# DC-DC.net
KiCad netlist of a schematic drawn in Altium Designer
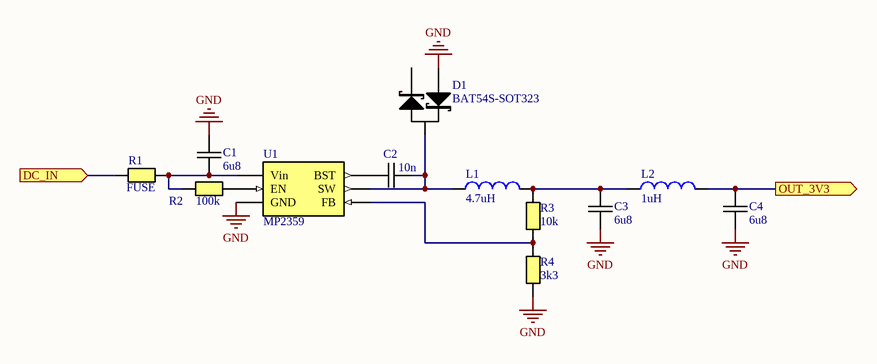
[diagram p0: DC-DC.SchDoc]

(export (version "E")
  (design (tool "Eeschema 10.0.6"))
  (components
    (comp (ref "C1")
      (value "6u8")
      (footprint "CAPC0805(2012)75_N")
      (description "Ceramic capacitor Medium density")
      (libsource (lib "Discrete_Passive_RCL") (part "Capacitor M"))
    )
    (comp (ref "C2")
      (value "10n")
      (footprint "CAPC0603(1608)55_N")
      (description "Ceramic capacitor Medium density")
      (libsource (lib "Discrete_Passive_RCL") (part "Capacitor M"))
    )
    (comp (ref "C3")
      (value "6u8")
      (footprint "CAPC0805(2012)75_N")
      (description "Ceramic capacitor Medium density")
      (libsource (lib "Discrete_Passive_RCL") (part "Capacitor M"))
    )
    (comp (ref "C4")
      (value "6u8")
      (footprint "CAPC0805(2012)75_N")
      (description "Ceramic capacitor Medium density")
      (libsource (lib "Discrete_Passive_RCL") (part "Capacitor M"))
    )
    (comp (ref "D1")
      (value "BAT54S-SOT323")
      (footprint "SOT323-123")
      (description "DUAL SCHOTTKY DIODE SERIES")
      (fields
        (field (name "MANUFACTURER") "NXP Semiconductors")
        (field (name "MANUFACTURER PART NUMBER") "BAT54SW,115")
      )
      (libsource (lib "vh_altium_library") (part "BAT54S-SOT323"))
    )
    (comp (ref "L1")
      (value "IND")
      (footprint "C_1210")
      (fields (field (name "INDUCTANCE") "4.7uH"))
      (libsource (lib "MyLibAltium_v1") (part "Inductor"))
    )
    (comp (ref "L2")
      (value "IND")
      (footprint "C_1206")
      (fields (field (name "INDUCTANCE") "1uH"))
      (libsource (lib "MyLibAltium_v1") (part "Inductor"))
    )
    (comp (ref "R1")
      (value "100")
      (footprint "RESC0805(2012)_N")
      (description "Resistor Medium Density")
      (libsource (lib "Discrete_Passive_RCL") (part "Resistor M"))
    )
    (comp (ref "R2")
      (value "100k")
      (footprint "RESC0805(2012)_N")
      (description "Resistor Medium Density")
      (libsource (lib "Discrete_Passive_RCL") (part "Resistor M"))
    )
    (comp (ref "R3")
      (value "10k")
      (footprint "RESC0805(2012)_N")
      (description "Resistor Medium Density")
      (libsource (lib "") (part "Resistor M_1"))
    )
    (comp (ref "R4")
      (value "3k3")
      (footprint "RESC0805(2012)_N")
      (description "Resistor Medium Density")
      (libsource (lib "") (part "Resistor M_1"))
    )
    (comp (ref "U1")
      (value "MP2359")
      (footprint "TSOP23-6")
      (description "monolithic step-down switch  mode converter with a built-in power MOSFET")
      (libsource (lib "MyLibAltium_v1") (part "MP2359"))
    )
  )
  (nets
    (net (code "1") (name "/DC_IN") (class "Default")
      (node (ref "R1") (pin "1") (pinfunction "1_1") (pintype "passive"))
    )
    (net (code "2") (name "/OUT_3V3") (class "Default")
      (node (ref "C4") (pin "1") (pinfunction "1_1") (pintype "passive"))
      (node (ref "L2") (pin "2") (pinfunction "2_2") (pintype "passive"))
    )
    (net (code "3") (name "GND") (class "Default")
      (node (ref "C1") (pin "1") (pinfunction "1_1") (pintype "passive"))
      (node (ref "C3") (pin "2") (pinfunction "2_2") (pintype "passive"))
      (node (ref "C4") (pin "2") (pinfunction "2_2") (pintype "passive"))
      (node (ref "D1") (pin "1") (pinfunction "1_1") (pintype "passive"))
      (node (ref "R4") (pin "1") (pinfunction "1_1") (pintype "passive"))
      (node (ref "U1") (pin "2") (pinfunction "GND_2") (pintype "power_in"))
    )
    (net (code "4") (name "Net-(C3-Pad1)") (class "Default")
      (node (ref "C3") (pin "1") (pinfunction "1_1") (pintype "passive"))
      (node (ref "L1") (pin "2") (pinfunction "2_2") (pintype "passive"))
      (node (ref "L2") (pin "1") (pinfunction "1_1") (pintype "passive"))
      (node (ref "R3") (pin "2") (pinfunction "2_2") (pintype "passive"))
    )
    (net (code "5") (name "Net-(U1-BST)") (class "Default")
      (node (ref "C2") (pin "1") (pinfunction "1_1") (pintype "passive"))
      (node (ref "U1") (pin "1") (pinfunction "BST_1") (pintype "output"))
    )
    (net (code "6") (name "Net-(U1-EN)") (class "Default")
      (node (ref "R2") (pin "2") (pinfunction "2_2") (pintype "passive"))
      (node (ref "U1") (pin "4") (pinfunction "EN_4") (pintype "input"))
    )
    (net (code "7") (name "Net-(U1-FB)") (class "Default")
      (node (ref "R3") (pin "1") (pinfunction "1_1") (pintype "passive"))
      (node (ref "R4") (pin "2") (pinfunction "2_2") (pintype "passive"))
      (node (ref "U1") (pin "3") (pinfunction "FB_3") (pintype "input"))
    )
    (net (code "8") (name "Net-(U1-SW)") (class "Default")
      (node (ref "C2") (pin "2") (pinfunction "2_2") (pintype "passive"))
      (node (ref "D1") (pin "3") (pinfunction "3_3") (pintype "passive"))
      (node (ref "L1") (pin "1") (pinfunction "1_1") (pintype "passive"))
      (node (ref "U1") (pin "6") (pinfunction "SW_6") (pintype "output"))
    )
    (net (code "9") (name "Net-(U1-Vin)") (class "Default")
      (node (ref "C1") (pin "2") (pinfunction "2_2") (pintype "passive"))
      (node (ref "R1") (pin "2") (pinfunction "2_2") (pintype "passive"))
      (node (ref "R2") (pin "1") (pinfunction "1_1") (pintype "passive"))
      (node (ref "U1") (pin "5") (pinfunction "Vin_5") (pintype "power_in"))
    )
    (net (code "10") (name "unconnected-(D1-Pad2)") (class "Default")
      (node (ref "D1") (pin "2") (pinfunction "2_2") (pintype "passive"))
    )
  )
)
